# rc6551z00_v1.net
KiCad netlist of a schematic drawn in EAGLE
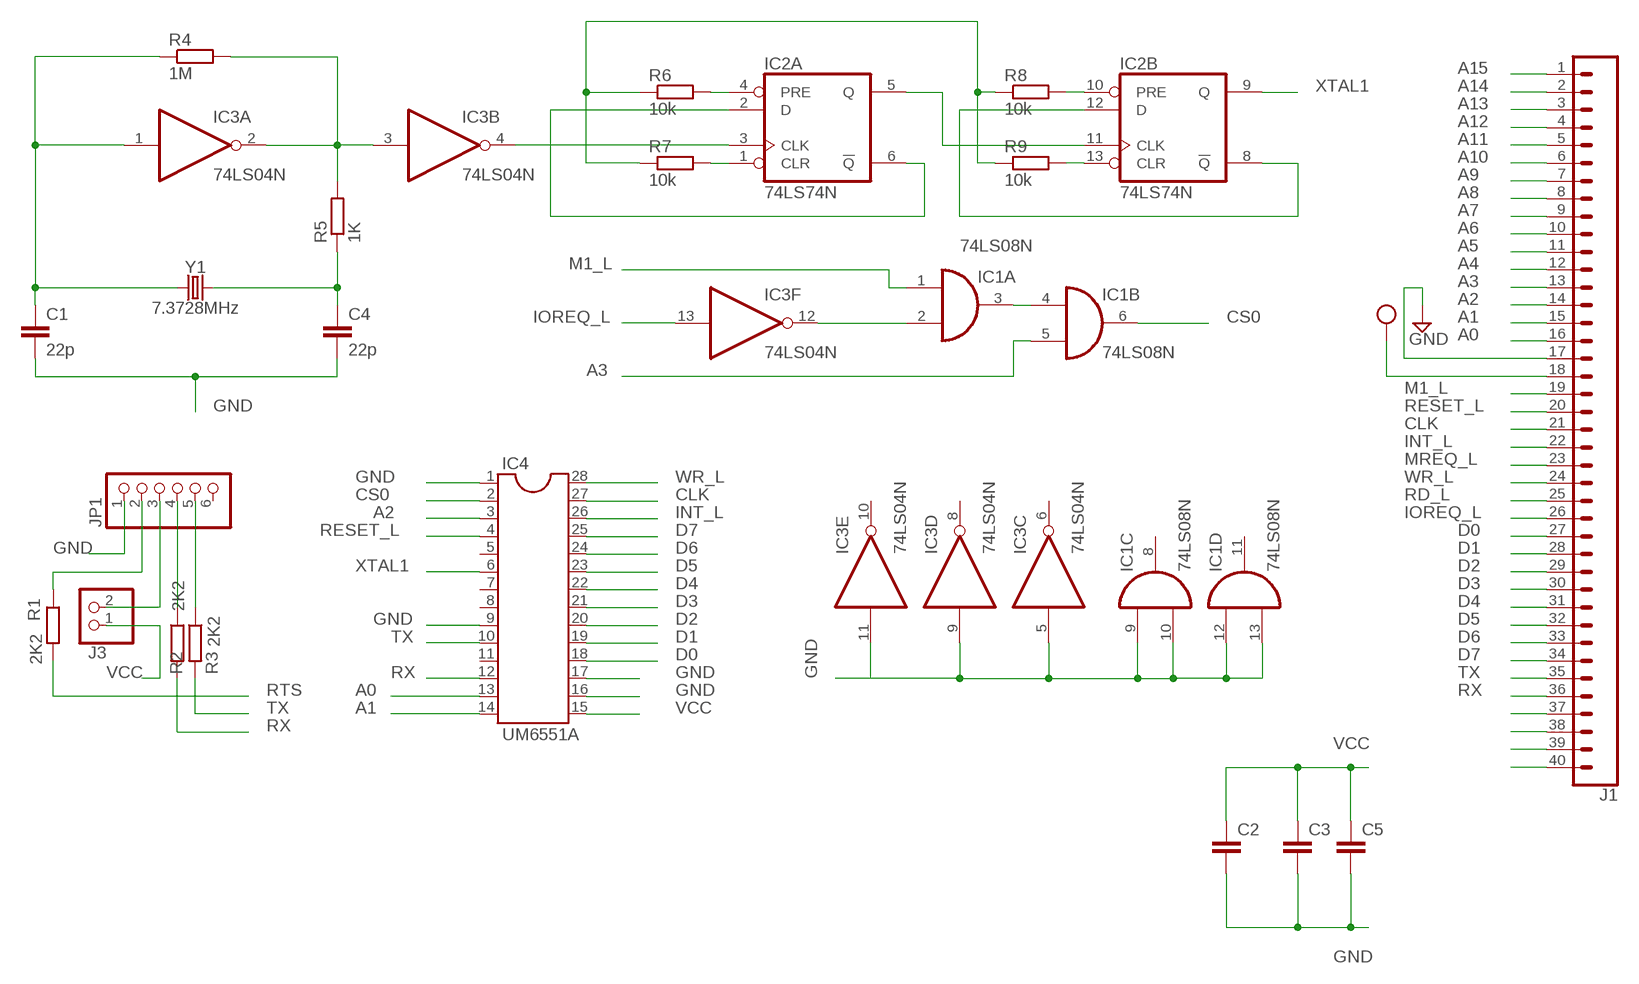
[diagram p0: schematic, sheet 1]

(export (version "E")
  (design (tool "Eeschema 10.0.6"))
  (components
    (comp (ref "C1")
      (value "22p")
      (footprint "eagle-import:C025-024X044")
      (libsource (lib "eagle-import") (part "rcl_334_C-EU025-024X044"))
    )
    (comp (ref "C2")
      (value "C-EU050-025X075")
      (footprint "eagle-import:C050-025X075")
      (libsource (lib "eagle-import") (part "C-EU050-025X075"))
    )
    (comp (ref "C3")
      (value "C-EU050-025X075")
      (footprint "eagle-import:C050-025X075")
      (libsource (lib "eagle-import") (part "C-EU050-025X075"))
    )
    (comp (ref "C4")
      (value "22p")
      (footprint "eagle-import:C025-024X044")
      (libsource (lib "eagle-import") (part "rcl_334_C-EU025-024X044"))
    )
    (comp (ref "C5")
      (value "C-EU050-025X075")
      (footprint "eagle-import:C050-025X075")
      (libsource (lib "eagle-import") (part "C-EU050-025X075"))
    )
    (comp (ref "IC1")
      (value "74LS08N")
      (footprint "eagle-import:DIL14")
      (libsource (lib "eagle-import") (part "7408NLS"))
    )
    (comp (ref "IC2")
      (value "74LS74N")
      (footprint "eagle-import:DIL14")
      (libsource (lib "eagle-import") (part "7474NLS"))
    )
    (comp (ref "IC3")
      (value "74LS04N")
      (footprint "eagle-import:DIL14")
      (libsource (lib "eagle-import") (part "7404NLS"))
    )
    (comp (ref "IC4")
      (value "UM6551A")
      (footprint "eagle-import:DIL28-6")
      (libsource (lib "eagle-import") (part "DIL28"))
    )
    (comp (ref "J1")
      (value "CONN_40OFFSET")
      (footprint "eagle-import:1X40_OFFSET")
      (libsource (lib "eagle-import") (part "CONN_40OFFSET"))
    )
    (comp (ref "J3")
      (value "PINHD-1X2")
      (footprint "eagle-import:1X02")
      (libsource (lib "eagle-import") (part "PINHD-1X2"))
    )
    (comp (ref "JP1")
      (value "PINHD-1X6")
      (footprint "eagle-import:1X06")
      (libsource (lib "eagle-import") (part "PINHD-1X6"))
    )
    (comp (ref "R1")
      (value "2K2")
      (footprint "eagle-import:0204_7")
      (libsource (lib "eagle-import") (part "R-EU_0204/7"))
    )
    (comp (ref "R2")
      (value "2K2")
      (footprint "eagle-import:0204_7")
      (libsource (lib "eagle-import") (part "R-EU_0204/7"))
    )
    (comp (ref "R3")
      (value "2K2")
      (footprint "eagle-import:0204_7")
      (libsource (lib "eagle-import") (part "R-EU_0204/7"))
    )
    (comp (ref "R4")
      (value "1M")
      (footprint "eagle-import:0204_5")
      (libsource (lib "eagle-import") (part "R-EU_0204/5"))
    )
    (comp (ref "R5")
      (value "1K")
      (footprint "eagle-import:0204_5")
      (libsource (lib "eagle-import") (part "R-EU_0204/5"))
    )
    (comp (ref "R6")
      (value "10k")
      (footprint "eagle-import:0204_7")
      (libsource (lib "eagle-import") (part "R-EU_0204/7"))
    )
    (comp (ref "R7")
      (value "10k")
      (footprint "eagle-import:0204_7")
      (libsource (lib "eagle-import") (part "R-EU_0204/7"))
    )
    (comp (ref "R8")
      (value "10k")
      (footprint "eagle-import:0204_7")
      (libsource (lib "eagle-import") (part "R-EU_0204/7"))
    )
    (comp (ref "R9")
      (value "10k")
      (footprint "eagle-import:0204_7")
      (libsource (lib "eagle-import") (part "R-EU_0204/7"))
    )
    (comp (ref "Y1")
      (value "7.3728MHz")
      (footprint "eagle-import:HC49U")
      (libsource (lib "eagle-import") (part "CRYSTALPTH-HC49UV"))
    )
  )
  (nets
    (net (code "1") (name "/A0") (class "Default")
      (node (ref "IC4") (pin "13") (pinfunction "13_13") (pintype "passive"))
      (node (ref "J1") (pin "16") (pinfunction "16_16") (pintype "passive"))
    )
    (net (code "2") (name "/A1") (class "Default")
      (node (ref "IC4") (pin "14") (pinfunction "14_14") (pintype "passive"))
      (node (ref "J1") (pin "15") (pinfunction "15_15") (pintype "passive"))
    )
    (net (code "3") (name "/A2") (class "Default")
      (node (ref "IC4") (pin "3") (pinfunction "3_3") (pintype "passive"))
      (node (ref "J1") (pin "14") (pinfunction "14_14") (pintype "passive"))
    )
    (net (code "4") (name "/A3") (class "Default")
      (node (ref "IC1") (pin "5") (pinfunction "I1_5") (pintype "input"))
      (node (ref "J1") (pin "13") (pinfunction "13_13") (pintype "passive"))
    )
    (net (code "5") (name "/A4") (class "Default")
      (node (ref "J1") (pin "12") (pinfunction "12_12") (pintype "passive"))
    )
    (net (code "6") (name "/A5") (class "Default")
      (node (ref "J1") (pin "11") (pinfunction "11_11") (pintype "passive"))
    )
    (net (code "7") (name "/A6") (class "Default")
      (node (ref "J1") (pin "10") (pinfunction "10_10") (pintype "passive"))
    )
    (net (code "8") (name "/A7") (class "Default")
      (node (ref "J1") (pin "9") (pinfunction "9_9") (pintype "passive"))
    )
    (net (code "9") (name "/A8") (class "Default")
      (node (ref "J1") (pin "8") (pinfunction "8_8") (pintype "passive"))
    )
    (net (code "10") (name "/A9") (class "Default")
      (node (ref "J1") (pin "7") (pinfunction "7_7") (pintype "passive"))
    )
    (net (code "11") (name "/A10") (class "Default")
      (node (ref "J1") (pin "6") (pinfunction "6_6") (pintype "passive"))
    )
    (net (code "12") (name "/A11") (class "Default")
      (node (ref "J1") (pin "5") (pinfunction "5_5") (pintype "passive"))
    )
    (net (code "13") (name "/A12") (class "Default")
      (node (ref "J1") (pin "4") (pinfunction "4_4") (pintype "passive"))
    )
    (net (code "14") (name "/A13") (class "Default")
      (node (ref "J1") (pin "3") (pinfunction "3_3") (pintype "passive"))
    )
    (net (code "15") (name "/A14") (class "Default")
      (node (ref "J1") (pin "2") (pinfunction "2_2") (pintype "passive"))
    )
    (net (code "16") (name "/A15") (class "Default")
      (node (ref "J1") (pin "1") (pinfunction "1_1") (pintype "passive"))
    )
    (net (code "17") (name "/CLK") (class "Default")
      (node (ref "IC4") (pin "27") (pinfunction "27_27") (pintype "passive"))
      (node (ref "J1") (pin "21") (pinfunction "21_21") (pintype "passive"))
    )
    (net (code "18") (name "/CS0") (class "Default")
      (node (ref "IC1") (pin "6") (pinfunction "O_6") (pintype "output"))
      (node (ref "IC4") (pin "2") (pinfunction "2_2") (pintype "passive"))
    )
    (net (code "19") (name "/D0") (class "Default")
      (node (ref "IC4") (pin "18") (pinfunction "18_18") (pintype "passive"))
      (node (ref "J1") (pin "27") (pinfunction "27_27") (pintype "passive"))
    )
    (net (code "20") (name "/D1") (class "Default")
      (node (ref "IC4") (pin "19") (pinfunction "19_19") (pintype "passive"))
      (node (ref "J1") (pin "28") (pinfunction "28_28") (pintype "passive"))
    )
    (net (code "21") (name "/D2") (class "Default")
      (node (ref "IC4") (pin "20") (pinfunction "20_20") (pintype "passive"))
      (node (ref "J1") (pin "29") (pinfunction "29_29") (pintype "passive"))
    )
    (net (code "22") (name "/D3") (class "Default")
      (node (ref "IC4") (pin "21") (pinfunction "21_21") (pintype "passive"))
      (node (ref "J1") (pin "30") (pinfunction "30_30") (pintype "passive"))
    )
    (net (code "23") (name "/D4") (class "Default")
      (node (ref "IC4") (pin "22") (pinfunction "22_22") (pintype "passive"))
      (node (ref "J1") (pin "31") (pinfunction "31_31") (pintype "passive"))
    )
    (net (code "24") (name "/D5") (class "Default")
      (node (ref "IC4") (pin "23") (pinfunction "23_23") (pintype "passive"))
      (node (ref "J1") (pin "32") (pinfunction "32_32") (pintype "passive"))
    )
    (net (code "25") (name "/D6") (class "Default")
      (node (ref "IC4") (pin "24") (pinfunction "24_24") (pintype "passive"))
      (node (ref "J1") (pin "33") (pinfunction "33_33") (pintype "passive"))
    )
    (net (code "26") (name "/D7") (class "Default")
      (node (ref "IC4") (pin "25") (pinfunction "25_25") (pintype "passive"))
      (node (ref "J1") (pin "34") (pinfunction "34_34") (pintype "passive"))
    )
    (net (code "27") (name "/INT_L") (class "Default")
      (node (ref "IC4") (pin "26") (pinfunction "26_26") (pintype "passive"))
      (node (ref "J1") (pin "22") (pinfunction "22_22") (pintype "passive"))
    )
    (net (code "28") (name "/IOREQ_L") (class "Default")
      (node (ref "IC3") (pin "13") (pinfunction "I_13") (pintype "input"))
      (node (ref "J1") (pin "26") (pinfunction "26_26") (pintype "passive"))
    )
    (net (code "29") (name "/M1_L") (class "Default")
      (node (ref "IC1") (pin "1") (pinfunction "I0_1") (pintype "input"))
      (node (ref "J1") (pin "19") (pinfunction "19_19") (pintype "passive"))
    )
    (net (code "30") (name "/MREQ_L") (class "Default")
      (node (ref "J1") (pin "23") (pinfunction "23_23") (pintype "passive"))
    )
    (net (code "31") (name "/RD_L") (class "Default")
      (node (ref "J1") (pin "25") (pinfunction "25_25") (pintype "passive"))
    )
    (net (code "32") (name "/RESET_L") (class "Default")
      (node (ref "IC4") (pin "4") (pinfunction "4_4") (pintype "passive"))
      (node (ref "J1") (pin "20") (pinfunction "20_20") (pintype "passive"))
    )
    (net (code "33") (name "/RTS") (class "Default")
      (node (ref "R1") (pin "2") (pinfunction "2_2") (pintype "passive"))
    )
    (net (code "34") (name "/RX") (class "Default")
      (node (ref "IC4") (pin "12") (pinfunction "12_12") (pintype "passive"))
      (node (ref "J1") (pin "36") (pinfunction "36_36") (pintype "passive"))
      (node (ref "R2") (pin "2") (pinfunction "2_2") (pintype "passive"))
    )
    (net (code "35") (name "/TX") (class "Default")
      (node (ref "IC4") (pin "10") (pinfunction "10_10") (pintype "passive"))
      (node (ref "J1") (pin "35") (pinfunction "35_35") (pintype "passive"))
      (node (ref "R3") (pin "2") (pinfunction "2_2") (pintype "passive"))
    )
    (net (code "36") (name "/WR_L") (class "Default")
      (node (ref "IC4") (pin "28") (pinfunction "28_28") (pintype "passive"))
      (node (ref "J1") (pin "24") (pinfunction "24_24") (pintype "passive"))
    )
    (net (code "37") (name "/XTAL1") (class "Default")
      (node (ref "IC2") (pin "9") (pinfunction "Q_9") (pintype "output"))
      (node (ref "IC4") (pin "6") (pinfunction "6_6") (pintype "passive"))
    )
    (net (code "38") (name "GND") (class "Default")
      (node (ref "C1") (pin "2") (pinfunction "2_2") (pintype "passive"))
      (node (ref "C2") (pin "2") (pinfunction "2_2") (pintype "passive"))
      (node (ref "C3") (pin "2") (pinfunction "2_2") (pintype "passive"))
      (node (ref "C4") (pin "2") (pinfunction "2_2") (pintype "passive"))
      (node (ref "C5") (pin "2") (pinfunction "2_2") (pintype "passive"))
      (node (ref "IC1") (pin "10") (pinfunction "I1_10") (pintype "input"))
      (node (ref "IC1") (pin "12") (pinfunction "I0_12") (pintype "input"))
      (node (ref "IC1") (pin "13") (pinfunction "I1_13") (pintype "input"))
      (node (ref "IC1") (pin "9") (pinfunction "I0_9") (pintype "input"))
      (node (ref "IC3") (pin "5") (pinfunction "I_5") (pintype "input"))
      (node (ref "IC3") (pin "9") (pinfunction "I_9") (pintype "input"))
      (node (ref "IC4") (pin "1") (pinfunction "1_1") (pintype "passive"))
      (node (ref "IC4") (pin "16") (pinfunction "16_16") (pintype "passive"))
      (node (ref "IC4") (pin "17") (pinfunction "17_17") (pintype "passive"))
      (node (ref "IC4") (pin "9") (pinfunction "9_9") (pintype "passive"))
      (node (ref "J1") (pin "17") (pinfunction "17_17") (pintype "passive"))
      (node (ref "JP1") (pin "1") (pinfunction "1_1") (pintype "passive"))
    )
    (net (code "39") (name "Net-(C4-Pad1)") (class "Default")
      (node (ref "C4") (pin "1") (pinfunction "1_1") (pintype "passive"))
      (node (ref "R5") (pin "1") (pinfunction "1_1") (pintype "passive"))
      (node (ref "Y1") (pin "2") (pinfunction "2_2") (pintype "passive"))
    )
    (net (code "40") (name "Net-(IC1A-I1)") (class "Default")
      (node (ref "IC1") (pin "2") (pinfunction "I1_2") (pintype "input"))
      (node (ref "IC3") (pin "12") (pinfunction "O_12") (pintype "output"))
    )
    (net (code "41") (name "Net-(IC1A-O)") (class "Default")
      (node (ref "IC1") (pin "3") (pinfunction "O_3") (pintype "output"))
      (node (ref "IC1") (pin "4") (pinfunction "I0_4") (pintype "input"))
    )
    (net (code "42") (name "Net-(IC2A-CLK)") (class "Default")
      (node (ref "IC2") (pin "3") (pinfunction "CLK_3") (pintype "input"))
      (node (ref "IC3") (pin "4") (pinfunction "O_4") (pintype "output"))
    )
    (net (code "43") (name "Net-(IC2A-CLR)") (class "Default")
      (node (ref "IC2") (pin "1") (pinfunction "CLR_1") (pintype "input"))
      (node (ref "R7") (pin "2") (pinfunction "2_2") (pintype "passive"))
    )
    (net (code "44") (name "Net-(IC2A-D)") (class "Default")
      (node (ref "IC2") (pin "2") (pinfunction "D_2") (pintype "input"))
      (node (ref "IC2") (pin "6") (pinfunction "~{Q}_6") (pintype "output"))
    )
    (net (code "45") (name "Net-(IC2A-PRE)") (class "Default")
      (node (ref "IC2") (pin "4") (pinfunction "PRE_4") (pintype "input"))
      (node (ref "R6") (pin "2") (pinfunction "2_2") (pintype "passive"))
    )
    (net (code "46") (name "Net-(IC2A-Q)") (class "Default")
      (node (ref "IC2") (pin "11") (pinfunction "CLK_11") (pintype "input"))
      (node (ref "IC2") (pin "5") (pinfunction "Q_5") (pintype "output"))
    )
    (net (code "47") (name "Net-(IC2B-CLR)") (class "Default")
      (node (ref "IC2") (pin "13") (pinfunction "CLR_13") (pintype "input"))
      (node (ref "R9") (pin "2") (pinfunction "2_2") (pintype "passive"))
    )
    (net (code "48") (name "Net-(IC2B-D)") (class "Default")
      (node (ref "IC2") (pin "12") (pinfunction "D_12") (pintype "input"))
      (node (ref "IC2") (pin "8") (pinfunction "~{Q}_8") (pintype "output"))
    )
    (net (code "49") (name "Net-(IC2B-PRE)") (class "Default")
      (node (ref "IC2") (pin "10") (pinfunction "PRE_10") (pintype "input"))
      (node (ref "R8") (pin "2") (pinfunction "2_2") (pintype "passive"))
    )
    (net (code "50") (name "Net-(IC3A-I)") (class "Default")
      (node (ref "C1") (pin "1") (pinfunction "1_1") (pintype "passive"))
      (node (ref "IC3") (pin "1") (pinfunction "I_1") (pintype "input"))
      (node (ref "R4") (pin "1") (pinfunction "1_1") (pintype "passive"))
      (node (ref "Y1") (pin "1") (pinfunction "1_1") (pintype "passive"))
    )
    (net (code "51") (name "Net-(IC3A-O)") (class "Default")
      (node (ref "IC3") (pin "2") (pinfunction "O_2") (pintype "output"))
      (node (ref "IC3") (pin "3") (pinfunction "I_3") (pintype "input"))
      (node (ref "R4") (pin "2") (pinfunction "2_2") (pintype "passive"))
      (node (ref "R5") (pin "2") (pinfunction "2_2") (pintype "passive"))
    )
    (net (code "52") (name "Net-(J3-Pad2)") (class "Default")
      (node (ref "J3") (pin "2") (pinfunction "2_2") (pintype "passive"))
      (node (ref "JP1") (pin "3") (pinfunction "3_3") (pintype "passive"))
    )
    (net (code "53") (name "Net-(JP1-Pad2)") (class "Default")
      (node (ref "JP1") (pin "2") (pinfunction "2_2") (pintype "passive"))
      (node (ref "R1") (pin "1") (pinfunction "1_1") (pintype "passive"))
    )
    (net (code "54") (name "Net-(JP1-Pad4)") (class "Default")
      (node (ref "JP1") (pin "4") (pinfunction "4_4") (pintype "passive"))
      (node (ref "R2") (pin "1") (pinfunction "1_1") (pintype "passive"))
    )
    (net (code "55") (name "Net-(JP1-Pad5)") (class "Default")
      (node (ref "JP1") (pin "5") (pinfunction "5_5") (pintype "passive"))
      (node (ref "R3") (pin "1") (pinfunction "1_1") (pintype "passive"))
    )
    (net (code "56") (name "Net-(R6-Pad1)") (class "Default")
      (node (ref "R6") (pin "1") (pinfunction "1_1") (pintype "passive"))
      (node (ref "R7") (pin "1") (pinfunction "1_1") (pintype "passive"))
      (node (ref "R8") (pin "1") (pinfunction "1_1") (pintype "passive"))
      (node (ref "R9") (pin "1") (pinfunction "1_1") (pintype "passive"))
    )
    (net (code "57") (name "VCC") (class "Default")
      (node (ref "C2") (pin "1") (pinfunction "1_1") (pintype "passive"))
      (node (ref "C3") (pin "1") (pinfunction "1_1") (pintype "passive"))
      (node (ref "C5") (pin "1") (pinfunction "1_1") (pintype "passive"))
      (node (ref "IC4") (pin "15") (pinfunction "15_15") (pintype "passive"))
      (node (ref "J1") (pin "18") (pinfunction "18_18") (pintype "passive"))
      (node (ref "J3") (pin "1") (pinfunction "1_1") (pintype "passive"))
    )
    (net (code "58") (name "unconnected-(IC1C-O-Pad8)") (class "Default")
      (node (ref "IC1") (pin "8") (pinfunction "O_8") (pintype "output"))
    )
    (net (code "59") (name "unconnected-(IC1D-O-Pad11)") (class "Default")
      (node (ref "IC1") (pin "11") (pinfunction "O_11") (pintype "output"))
    )
    (net (code "60") (name "unconnected-(IC3C-O-Pad6)") (class "Default")
      (node (ref "IC3") (pin "6") (pinfunction "O_6") (pintype "output"))
    )
    (net (code "61") (name "unconnected-(IC3D-O-Pad8)") (class "Default")
      (node (ref "IC3") (pin "8") (pinfunction "O_8") (pintype "output"))
    )
    (net (code "62") (name "unconnected-(IC3E-I-Pad11)") (class "Default")
      (node (ref "IC3") (pin "11") (pinfunction "I_11") (pintype "input"))
    )
    (net (code "63") (name "unconnected-(IC3E-O-Pad10)") (class "Default")
      (node (ref "IC3") (pin "10") (pinfunction "O_10") (pintype "output"))
    )
    (net (code "64") (name "unconnected-(IC4-Pad5)") (class "Default")
      (node (ref "IC4") (pin "5") (pinfunction "5_5") (pintype "passive"))
    )
    (net (code "65") (name "unconnected-(IC4-Pad7)") (class "Default")
      (node (ref "IC4") (pin "7") (pinfunction "7_7") (pintype "passive"))
    )
    (net (code "66") (name "unconnected-(IC4-Pad8)") (class "Default")
      (node (ref "IC4") (pin "8") (pinfunction "8_8") (pintype "passive"))
    )
    (net (code "67") (name "unconnected-(IC4-Pad11)") (class "Default")
      (node (ref "IC4") (pin "11") (pinfunction "11_11") (pintype "passive"))
    )
    (net (code "68") (name "unconnected-(J1-Pad37)") (class "Default")
      (node (ref "J1") (pin "37") (pinfunction "37_37") (pintype "passive"))
    )
    (net (code "69") (name "unconnected-(J1-Pad38)") (class "Default")
      (node (ref "J1") (pin "38") (pinfunction "38_38") (pintype "passive"))
    )
    (net (code "70") (name "unconnected-(J1-Pad39)") (class "Default")
      (node (ref "J1") (pin "39") (pinfunction "39_39") (pintype "passive"))
    )
    (net (code "71") (name "unconnected-(J1-Pad40)") (class "Default")
      (node (ref "J1") (pin "40") (pinfunction "40_40") (pintype "passive"))
    )
    (net (code "72") (name "unconnected-(JP1-Pad6)") (class "Default")
      (node (ref "JP1") (pin "6") (pinfunction "6_6") (pintype "passive"))
    )
  )
)
